# rd.net
KiCad netlist of a schematic drawn in Altium Designer
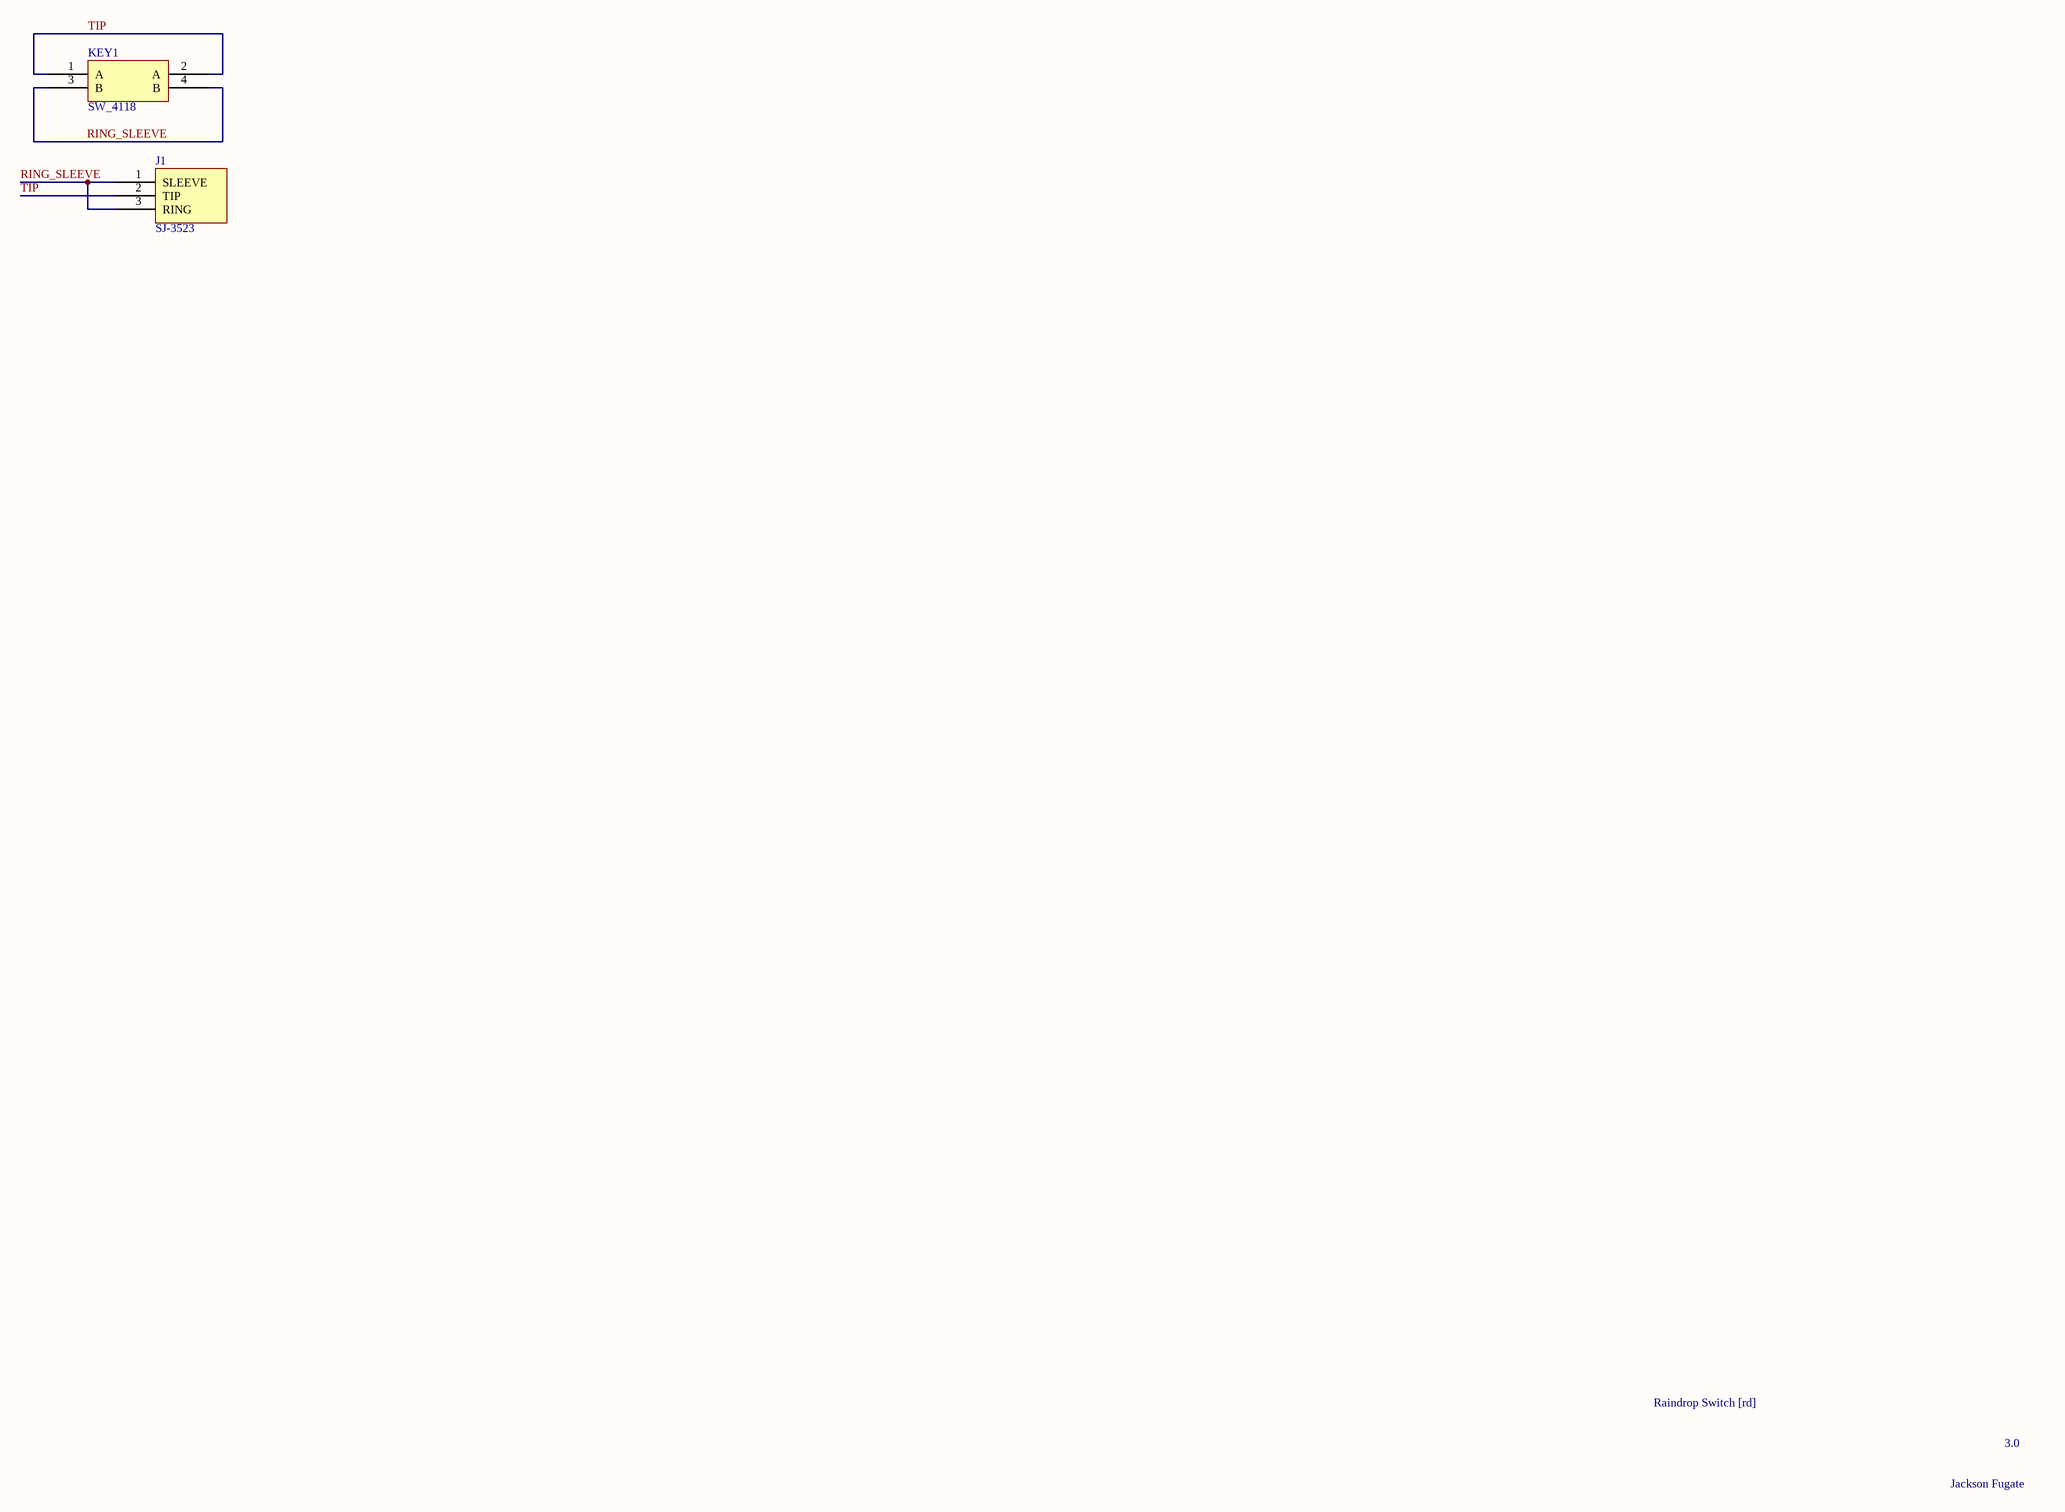
[diagram p0: rd.SchDoc]

(export (version "E")
  (design (tool "Eeschema 10.0.6"))
  (components
    (comp (ref "J1")
      (value "SJ-3523")
      (footprint "SJ-352X")
      (libsource (lib "JF_master_lib") (part "SJ-3523"))
    )
    (comp (ref "KEY1")
      (value "SW_4118")
      (footprint "SW_4118")
      (libsource (lib "JF_master_lib") (part "SW_4118"))
    )
  )
  (nets
    (net (code "1") (name "/RING_SLEEVE") (class "Default")
      (node (ref "J1") (pin "1") (pinfunction "SLEEVE_1") (pintype "passive"))
      (node (ref "J1") (pin "3") (pinfunction "RING_3") (pintype "passive"))
      (node (ref "KEY1") (pin "3") (pinfunction "B_3") (pintype "passive"))
      (node (ref "KEY1") (pin "4") (pinfunction "B_4") (pintype "passive"))
    )
    (net (code "2") (name "/TIP") (class "Default")
      (node (ref "J1") (pin "2") (pinfunction "TIP_2") (pintype "passive"))
      (node (ref "KEY1") (pin "1") (pinfunction "A_1") (pintype "passive"))
      (node (ref "KEY1") (pin "2") (pinfunction "A_2") (pintype "passive"))
    )
  )
)
